# SNES_Mini_SD.net
KiCad netlist of a schematic drawn in EAGLE
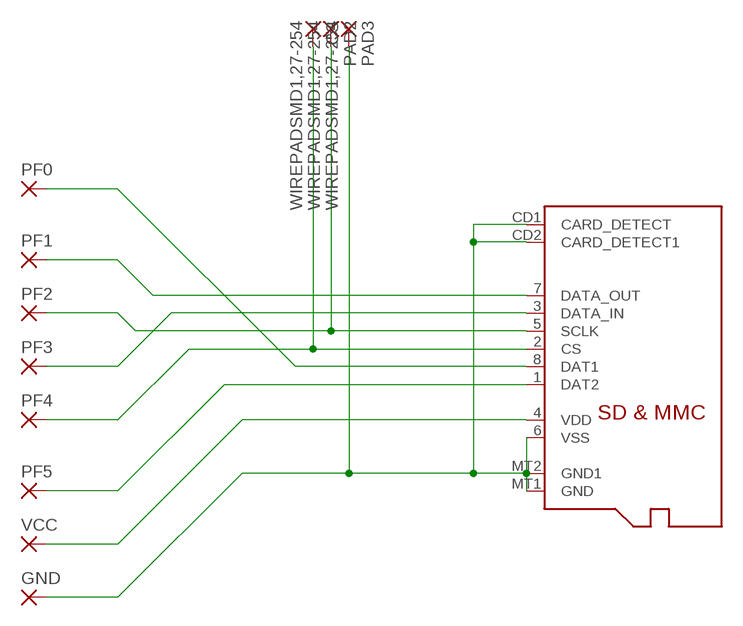
[diagram p0: schematic, sheet 1]

(export (version "E")
  (design (tool "Eeschema 10.0.6"))
  (components
    (comp (ref "CS")
      (value "WIREPADSMD1,27-254")
      (footprint "eagle-import:SMD1,27-2,54")
      (libsource (lib "eagle-import") (part "WIREPADSMD1,27-254"))
    )
    (comp (ref "GND")
      (value "2,15/1,0")
      (footprint "eagle-import:2,15_1,0")
      (libsource (lib "eagle-import") (part "2,15/1,0"))
    )
    (comp (ref "PAD2")
      (value "WIREPADSMD1,27-254")
      (footprint "eagle-import:SMD1,27-2,54")
      (libsource (lib "eagle-import") (part "WIREPADSMD1,27-254"))
    )
    (comp (ref "PAD3")
      (value "WIREPADSMD1,27-254")
      (footprint "eagle-import:SMD1,27-2,54")
      (libsource (lib "eagle-import") (part "WIREPADSMD1,27-254"))
    )
    (comp (ref "PF0")
      (value "2,15/1,0")
      (footprint "eagle-import:2,15_1,0")
      (libsource (lib "eagle-import") (part "2,15/1,0"))
    )
    (comp (ref "PF1")
      (value "2,15/1,0")
      (footprint "eagle-import:2,15_1,0")
      (libsource (lib "eagle-import") (part "2,15/1,0"))
    )
    (comp (ref "PF2")
      (value "2,15/1,0")
      (footprint "eagle-import:2,15_1,0")
      (libsource (lib "eagle-import") (part "2,15/1,0"))
    )
    (comp (ref "PF3")
      (value "2,15/1,0")
      (footprint "eagle-import:2,15_1,0")
      (libsource (lib "eagle-import") (part "2,15/1,0"))
    )
    (comp (ref "PF4")
      (value "2,15/1,0")
      (footprint "eagle-import:2,15_1,0")
      (libsource (lib "eagle-import") (part "2,15/1,0"))
    )
    (comp (ref "PF5")
      (value "2,15/1,0")
      (footprint "eagle-import:2,15_1,0")
      (libsource (lib "eagle-import") (part "2,15/1,0"))
    )
    (comp (ref "U$1")
      (value "MICROSD")
      (footprint "eagle-import:MICROSD")
      (libsource (lib "eagle-import") (part "MICROSD"))
    )
    (comp (ref "VCC")
      (value "2,15/1,0")
      (footprint "eagle-import:2,15_1,0")
      (libsource (lib "eagle-import") (part "2,15/1,0"))
    )
  )
  (nets
    (net (code "1") (name "Net-(CS-P)") (class "Default")
      (node (ref "CS") (pin "1") (pinfunction "P_1") (pintype "passive"))
      (node (ref "PF4") (pin "1") (pinfunction "P_1") (pintype "passive"))
      (node (ref "U$1") (pin "2") (pinfunction "CS_2") (pintype "input"))
    )
    (net (code "2") (name "Net-(GND-P)") (class "Default")
      (node (ref "GND") (pin "1") (pinfunction "P_1") (pintype "passive"))
      (node (ref "PAD3") (pin "1") (pinfunction "P_1") (pintype "passive"))
      (node (ref "U$1") (pin "6") (pinfunction "VSS_6") (pintype "power_in"))
      (node (ref "U$1") (pin "CD1") (pinfunction "CARD_DETECT_CD1") (pintype "passive"))
      (node (ref "U$1") (pin "CD2") (pinfunction "CARD_DETECT1_CD2") (pintype "passive"))
      (node (ref "U$1") (pin "MT1") (pinfunction "GND_MT1") (pintype "power_in"))
      (node (ref "U$1") (pin "MT2") (pinfunction "GND1_MT2") (pintype "power_in"))
    )
    (net (code "3") (name "Net-(PAD2-P)") (class "Default")
      (node (ref "PAD2") (pin "1") (pinfunction "P_1") (pintype "passive"))
      (node (ref "PF2") (pin "1") (pinfunction "P_1") (pintype "passive"))
      (node (ref "U$1") (pin "5") (pinfunction "SCLK_5") (pintype "input"))
    )
    (net (code "4") (name "Net-(PF0-P)") (class "Default")
      (node (ref "PF0") (pin "1") (pinfunction "P_1") (pintype "passive"))
      (node (ref "U$1") (pin "8") (pinfunction "DAT1_8") (pintype "bidirectional"))
    )
    (net (code "5") (name "Net-(PF1-P)") (class "Default")
      (node (ref "PF1") (pin "1") (pinfunction "P_1") (pintype "passive"))
      (node (ref "U$1") (pin "7") (pinfunction "DATA_OUT_7") (pintype "output"))
    )
    (net (code "6") (name "Net-(PF3-P)") (class "Default")
      (node (ref "PF3") (pin "1") (pinfunction "P_1") (pintype "passive"))
      (node (ref "U$1") (pin "3") (pinfunction "DATA_IN_3") (pintype "input"))
    )
    (net (code "7") (name "Net-(PF5-P)") (class "Default")
      (node (ref "PF5") (pin "1") (pinfunction "P_1") (pintype "passive"))
      (node (ref "U$1") (pin "1") (pinfunction "DAT2_1") (pintype "bidirectional"))
    )
    (net (code "8") (name "Net-(U$1-VDD)") (class "Default")
      (node (ref "U$1") (pin "4") (pinfunction "VDD_4") (pintype "power_in"))
      (node (ref "VCC") (pin "1") (pinfunction "P_1") (pintype "passive"))
    )
  )
)
